# car_bluetooth_v1_1.net
KiCad netlist of a schematic drawn in EAGLE
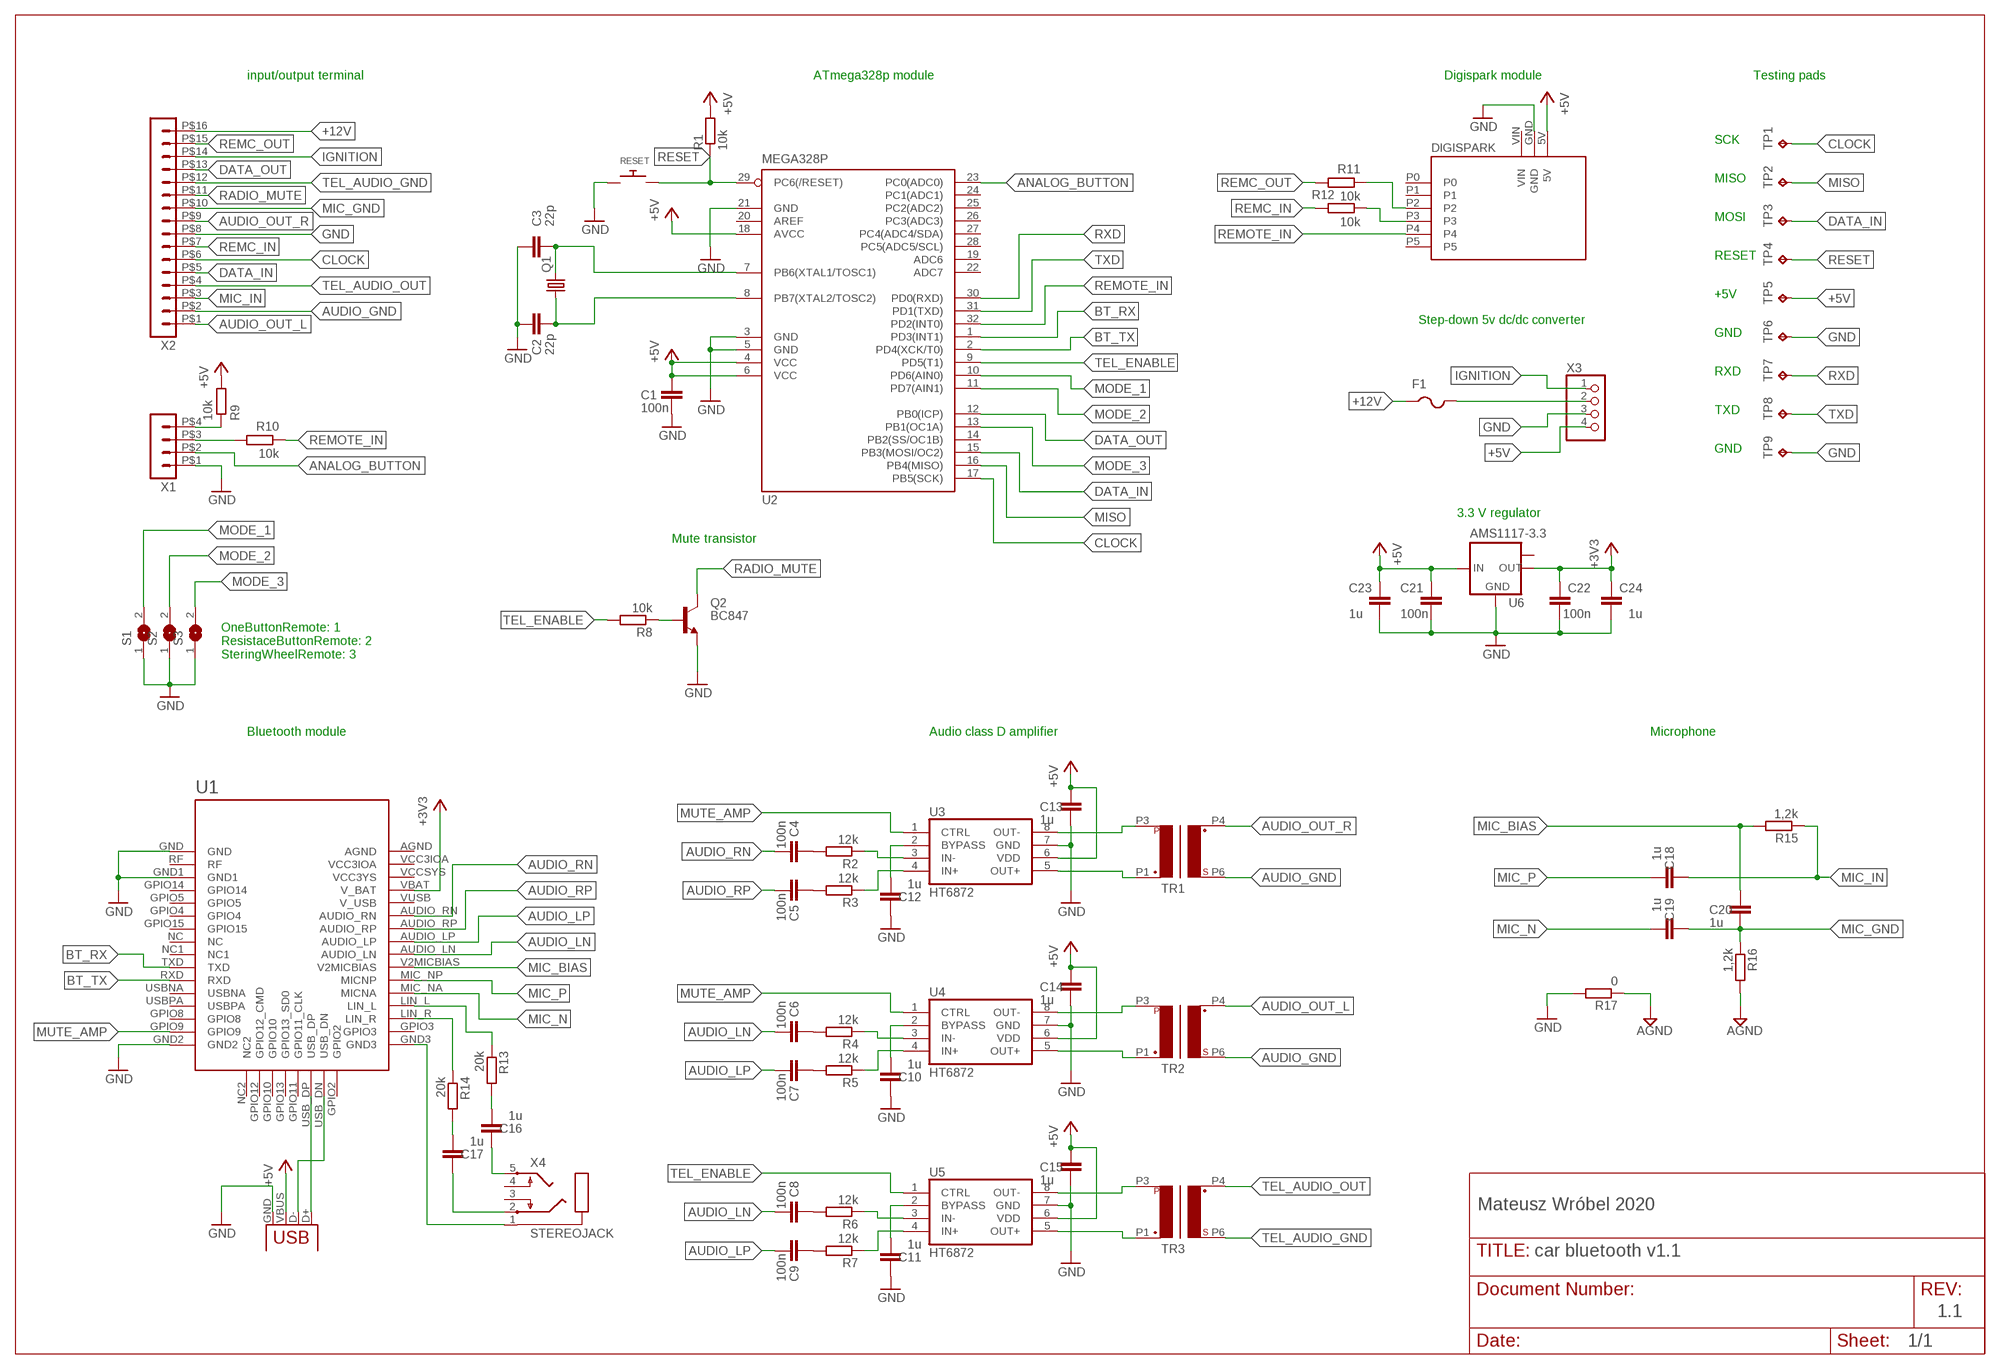
[diagram p0: schematic, sheet 1]

(export (version "E")
  (design (tool "Eeschema 10.0.6"))
  (components
    (comp (ref "C1")
      (value "100n")
      (footprint "eagle-import:C0805")
      (libsource (lib "eagle-import") (part "C-EUC0805"))
    )
    (comp (ref "C2")
      (value "22p")
      (footprint "eagle-import:C0805")
      (libsource (lib "eagle-import") (part "C-EUC0805"))
    )
    (comp (ref "C3")
      (value "22p")
      (footprint "eagle-import:C0805")
      (libsource (lib "eagle-import") (part "C-EUC0805"))
    )
    (comp (ref "C4")
      (value "100n")
      (footprint "eagle-import:C0805")
      (libsource (lib "eagle-import") (part "C-EUC0805"))
    )
    (comp (ref "C5")
      (value "100n")
      (footprint "eagle-import:C0805")
      (libsource (lib "eagle-import") (part "C-EUC0805"))
    )
    (comp (ref "C6")
      (value "100n")
      (footprint "eagle-import:C0805")
      (libsource (lib "eagle-import") (part "C-EUC0805"))
    )
    (comp (ref "C7")
      (value "100n")
      (footprint "eagle-import:C0805")
      (libsource (lib "eagle-import") (part "C-EUC0805"))
    )
    (comp (ref "C8")
      (value "100n")
      (footprint "eagle-import:C0805")
      (libsource (lib "eagle-import") (part "C-EUC0805"))
    )
    (comp (ref "C9")
      (value "100n")
      (footprint "eagle-import:C0805")
      (libsource (lib "eagle-import") (part "C-EUC0805"))
    )
    (comp (ref "C10")
      (value "1u")
      (footprint "eagle-import:C0805")
      (libsource (lib "eagle-import") (part "C-EUC0805"))
    )
    (comp (ref "C11")
      (value "1u")
      (footprint "eagle-import:C0805")
      (libsource (lib "eagle-import") (part "C-EUC0805"))
    )
    (comp (ref "C12")
      (value "1u")
      (footprint "eagle-import:C0805")
      (libsource (lib "eagle-import") (part "C-EUC0805"))
    )
    (comp (ref "C13")
      (value "1u")
      (footprint "eagle-import:C0805")
      (libsource (lib "eagle-import") (part "C-EUC0805"))
    )
    (comp (ref "C14")
      (value "1u")
      (footprint "eagle-import:C0805")
      (libsource (lib "eagle-import") (part "C-EUC0805"))
    )
    (comp (ref "C15")
      (value "1u")
      (footprint "eagle-import:C0805")
      (libsource (lib "eagle-import") (part "C-EUC0805"))
    )
    (comp (ref "C16")
      (value "1u")
      (footprint "eagle-import:C0805")
      (libsource (lib "eagle-import") (part "C-EUC0805"))
    )
    (comp (ref "C17")
      (value "1u")
      (footprint "eagle-import:C0805")
      (libsource (lib "eagle-import") (part "C-EUC0805"))
    )
    (comp (ref "C18")
      (value "1u")
      (footprint "eagle-import:C0805")
      (libsource (lib "eagle-import") (part "C-EUC0805"))
    )
    (comp (ref "C19")
      (value "1u")
      (footprint "eagle-import:C0805")
      (libsource (lib "eagle-import") (part "C-EUC0805"))
    )
    (comp (ref "C20")
      (value "1u")
      (footprint "eagle-import:C0805")
      (libsource (lib "eagle-import") (part "C-EUC0805"))
    )
    (comp (ref "C21")
      (value "100n")
      (footprint "eagle-import:C0805")
      (libsource (lib "eagle-import") (part "C-EUC0805"))
    )
    (comp (ref "C22")
      (value "100n")
      (footprint "eagle-import:C0805")
      (libsource (lib "eagle-import") (part "C-EUC0805"))
    )
    (comp (ref "C23")
      (value "1u")
      (footprint "eagle-import:C0805")
      (libsource (lib "eagle-import") (part "C-EUC0805"))
    )
    (comp (ref "C24")
      (value "1u")
      (footprint "eagle-import:C0805")
      (libsource (lib "eagle-import") (part "C-EUC0805"))
    )
    (comp (ref "F1")
      (value "PTCFUSE-1206")
      (footprint "eagle-import:R1206")
      (libsource (lib "eagle-import") (part "PTCFUSE-1206"))
    )
    (comp (ref "Q1")
      (value "CRYSTALHC49S")
      (footprint "eagle-import:HC49_S")
      (libsource (lib "eagle-import") (part "CRYSTALHC49S"))
    )
    (comp (ref "Q2")
      (value "BC847")
      (footprint "eagle-import:SOT23")
      (libsource (lib "eagle-import") (part "BC847SMDALT1"))
    )
    (comp (ref "R1")
      (value "10k")
      (footprint "eagle-import:R0805")
      (libsource (lib "eagle-import") (part "R-EU_R0805"))
    )
    (comp (ref "R2")
      (value "12k")
      (footprint "eagle-import:R0805")
      (libsource (lib "eagle-import") (part "R-EU_R0805"))
    )
    (comp (ref "R3")
      (value "12k")
      (footprint "eagle-import:R0805")
      (libsource (lib "eagle-import") (part "R-EU_R0805"))
    )
    (comp (ref "R4")
      (value "12k")
      (footprint "eagle-import:R0805")
      (libsource (lib "eagle-import") (part "R-EU_R0805"))
    )
    (comp (ref "R5")
      (value "12k")
      (footprint "eagle-import:R0805")
      (libsource (lib "eagle-import") (part "R-EU_R0805"))
    )
    (comp (ref "R6")
      (value "12k")
      (footprint "eagle-import:R0805")
      (libsource (lib "eagle-import") (part "R-EU_R0805"))
    )
    (comp (ref "R7")
      (value "12k")
      (footprint "eagle-import:R0805")
      (libsource (lib "eagle-import") (part "R-EU_R0805"))
    )
    (comp (ref "R8")
      (value "10k")
      (footprint "eagle-import:R0805")
      (libsource (lib "eagle-import") (part "R-EU_R0805"))
    )
    (comp (ref "R9")
      (value "10k")
      (footprint "eagle-import:R0805")
      (libsource (lib "eagle-import") (part "R-EU_R0805"))
    )
    (comp (ref "R10")
      (value "10k")
      (footprint "eagle-import:R0805")
      (libsource (lib "eagle-import") (part "R-EU_R0805"))
    )
    (comp (ref "R11")
      (value "10k")
      (footprint "eagle-import:R0805")
      (libsource (lib "eagle-import") (part "R-EU_R0805"))
    )
    (comp (ref "R12")
      (value "10k")
      (footprint "eagle-import:R0805")
      (libsource (lib "eagle-import") (part "R-EU_R0805"))
    )
    (comp (ref "R13")
      (value "20k")
      (footprint "eagle-import:R0805")
      (libsource (lib "eagle-import") (part "R-EU_R0805"))
    )
    (comp (ref "R14")
      (value "20k")
      (footprint "eagle-import:R0805")
      (libsource (lib "eagle-import") (part "R-EU_R0805"))
    )
    (comp (ref "R15")
      (value "1,2k")
      (footprint "eagle-import:R0805")
      (libsource (lib "eagle-import") (part "R-EU_R0805"))
    )
    (comp (ref "R16")
      (value "1,2k")
      (footprint "eagle-import:R0805")
      (libsource (lib "eagle-import") (part "R-EU_R0805"))
    )
    (comp (ref "R17")
      (value "0")
      (footprint "eagle-import:R0805")
      (libsource (lib "eagle-import") (part "R-EU_R0805"))
    )
    (comp (ref "RESET")
      (value "SWITCH_PUSHBUTTONSOFTTOUCHSMD_SJ")
      (footprint "eagle-import:PUSHBUTTON_SMD_SJ")
      (libsource (lib "eagle-import") (part "SWITCH_PUSHBUTTONSOFTTOUCHSMD_SJ"))
    )
    (comp (ref "S1") (value "SJ") (footprint "eagle-import:SJ") (libsource (lib "eagle-import") (part "SJ")))
    (comp (ref "S2") (value "SJ") (footprint "eagle-import:SJ") (libsource (lib "eagle-import") (part "SJ")))
    (comp (ref "S3") (value "SJ") (footprint "eagle-import:SJ") (libsource (lib "eagle-import") (part "SJ")))
    (comp (ref "TP1")
      (value "TPB1,27")
      (footprint "eagle-import:B1,27")
      (libsource (lib "eagle-import") (part "TPB1,27"))
    )
    (comp (ref "TP2")
      (value "TPB1,27")
      (footprint "eagle-import:B1,27")
      (libsource (lib "eagle-import") (part "TPB1,27"))
    )
    (comp (ref "TP3")
      (value "TPB1,27")
      (footprint "eagle-import:B1,27")
      (libsource (lib "eagle-import") (part "TPB1,27"))
    )
    (comp (ref "TP4")
      (value "TPB1,27")
      (footprint "eagle-import:B1,27")
      (libsource (lib "eagle-import") (part "TPB1,27"))
    )
    (comp (ref "TP5")
      (value "TPB1,27")
      (footprint "eagle-import:B1,27")
      (libsource (lib "eagle-import") (part "TPB1,27"))
    )
    (comp (ref "TP6")
      (value "TPB1,27")
      (footprint "eagle-import:B1,27")
      (libsource (lib "eagle-import") (part "TPB1,27"))
    )
    (comp (ref "TP7")
      (value "TPB1,27")
      (footprint "eagle-import:B1,27")
      (libsource (lib "eagle-import") (part "TPB1,27"))
    )
    (comp (ref "TP8")
      (value "TPB1,27")
      (footprint "eagle-import:B1,27")
      (libsource (lib "eagle-import") (part "TPB1,27"))
    )
    (comp (ref "TP9")
      (value "TPB1,27")
      (footprint "eagle-import:B1,27")
      (libsource (lib "eagle-import") (part "TPB1,27"))
    )
    (comp (ref "TR1")
      (value "AUDIO_R")
      (footprint "eagle-import:EI14")
      (libsource (lib "eagle-import") (part "AUDIO_ISOLATION_TRANSFORMER_EI14"))
    )
    (comp (ref "TR2")
      (value "AUDIO_L")
      (footprint "eagle-import:EI14")
      (libsource (lib "eagle-import") (part "AUDIO_ISOLATION_TRANSFORMER_EI14"))
    )
    (comp (ref "TR3")
      (value "AUDIO_MIC")
      (footprint "eagle-import:EI14")
      (libsource (lib "eagle-import") (part "AUDIO_ISOLATION_TRANSFORMER_EI14"))
    )
    (comp (ref "U$7")
      (value "DIGISPARK")
      (footprint "eagle-import:DIGISPARK")
      (libsource (lib "eagle-import") (part "DIGISPARK"))
    )
    (comp (ref "U1")
      (value "BK3266_BOARD")
      (footprint "eagle-import:40PIN_BOARD")
      (libsource (lib "eagle-import") (part "BK3266_BOARD"))
    )
    (comp (ref "U2")
      (value "MEGA328P")
      (footprint "eagle-import:TQFP32-08")
      (fields (field (name "MPN") "ATMEGA8-16AU"))
      (libsource (lib "eagle-import") (part "MEGA8-AI"))
    )
    (comp (ref "U3")
      (value "HT6872")
      (footprint "eagle-import:SO8")
      (libsource (lib "eagle-import") (part "HT6872"))
    )
    (comp (ref "U4")
      (value "HT6872")
      (footprint "eagle-import:SO8")
      (libsource (lib "eagle-import") (part "HT6872"))
    )
    (comp (ref "U5")
      (value "HT6872")
      (footprint "eagle-import:SO8")
      (libsource (lib "eagle-import") (part "HT6872"))
    )
    (comp (ref "U6")
      (value "AMS1117-3.3")
      (footprint "eagle-import:SOT223")
      (libsource (lib "eagle-import") (part "LM1117MPX-3.3"))
    )
    (comp (ref "X1")
      (value "HEADER_POS4_43045-0401")
      (footprint "eagle-import:43045-0400")
      (libsource (lib "eagle-import") (part "HEADER_POS4_?43045-0401"))
    )
    (comp (ref "X2")
      (value "HEADER_POS16_43045-1600")
      (footprint "eagle-import:43045-1600")
      (libsource (lib "eagle-import") (part "HEADER_POS16_?43045-1600"))
    )
    (comp (ref "X3")
      (value "PINHD-1X4")
      (footprint "eagle-import:1X04")
      (libsource (lib "eagle-import") (part "PINHD-1X4"))
    )
    (comp (ref "X4")
      (value "STEREOJACK")
      (footprint "eagle-import:STX3100")
      (libsource (lib "eagle-import") (part "STEREOJACK"))
    )
    (comp (ref "X5")
      (value "USB-A-H")
      (footprint "eagle-import:USB-A-H")
      (libsource (lib "eagle-import") (part "USB-A-H"))
    )
  )
  (nets
    (net (code "1") (name "+3V3") (class "Default")
      (node (ref "C22") (pin "2") (pinfunction "2_2") (pintype "passive"))
      (node (ref "C24") (pin "2") (pinfunction "2_2") (pintype "passive"))
      (node (ref "U1") (pin "VBAT") (pinfunction "V_BAT_VBAT") (pintype "bidirectional"))
      (node (ref "U6") (pin "2") (pinfunction "OUT_2") (pintype "passive"))
    )
    (net (code "2") (name "+5V") (class "Default")
      (node (ref "C1") (pin "1") (pinfunction "1_1") (pintype "passive"))
      (node (ref "C13") (pin "1") (pinfunction "1_1") (pintype "passive"))
      (node (ref "C14") (pin "1") (pinfunction "1_1") (pintype "passive"))
      (node (ref "C15") (pin "1") (pinfunction "1_1") (pintype "passive"))
      (node (ref "C21") (pin "1") (pinfunction "1_1") (pintype "passive"))
      (node (ref "C23") (pin "1") (pinfunction "1_1") (pintype "passive"))
      (node (ref "R1") (pin "2") (pinfunction "2_2") (pintype "passive"))
      (node (ref "R9") (pin "1") (pinfunction "1_1") (pintype "passive"))
      (node (ref "TP5") (pin "TP") (pinfunction "TP_TP") (pintype "input"))
      (node (ref "U$7") (pin "5V") (pinfunction "5V_5V") (pintype "bidirectional"))
      (node (ref "U2") (pin "18") (pinfunction "AVCC_18") (pintype "power_in"))
      (node (ref "U2") (pin "4") (pinfunction "VCC_4") (pintype "power_in"))
      (node (ref "U2") (pin "6") (pinfunction "VCC_6") (pintype "power_in"))
      (node (ref "U3") (pin "6") (pinfunction "VDD_6") (pintype "power_in"))
      (node (ref "U4") (pin "6") (pinfunction "VDD_6") (pintype "power_in"))
      (node (ref "U5") (pin "6") (pinfunction "VDD_6") (pintype "power_in"))
      (node (ref "U6") (pin "3") (pinfunction "IN_3") (pintype "input"))
      (node (ref "X3") (pin "4") (pinfunction "4_4") (pintype "passive"))
      (node (ref "X5") (pin "VBUS") (pinfunction "VBUS_VBUS") (pintype "bidirectional"))
    )
    (net (code "3") (name "+12V") (class "Default")
      (node (ref "F1") (pin "1") (pinfunction "1_1") (pintype "passive"))
      (node (ref "X2") (pin "P$16") (pinfunction "16_P$16") (pintype "passive"))
    )
    (net (code "4") (name "AGND") (class "Default")
      (node (ref "R16") (pin "2") (pinfunction "2_2") (pintype "passive"))
      (node (ref "R17") (pin "1") (pinfunction "1_1") (pintype "passive"))
    )
    (net (code "5") (name "ANALOG_BUTTON") (class "Default")
      (node (ref "U2") (pin "23") (pinfunction "PC0(ADC0)_23") (pintype "bidirectional"))
      (node (ref "X1") (pin "P$2") (pinfunction "2_P$2") (pintype "passive"))
    )
    (net (code "6") (name "AUDIO_GND") (class "Default")
      (node (ref "TR1") (pin "P6") (pinfunction "P4_P6") (pintype "bidirectional"))
      (node (ref "TR2") (pin "P6") (pinfunction "P4_P6") (pintype "bidirectional"))
      (node (ref "X2") (pin "P$2") (pinfunction "2_P$2") (pintype "passive"))
    )
    (net (code "7") (name "AUDIO_LN") (class "Default")
      (node (ref "C6") (pin "2") (pinfunction "2_2") (pintype "passive"))
      (node (ref "C8") (pin "2") (pinfunction "2_2") (pintype "passive"))
      (node (ref "U1") (pin "AUDIO_LN") (pinfunction "AUDIO_LN_AUDIO_LN") (pintype "bidirectional"))
    )
    (net (code "8") (name "AUDIO_LP") (class "Default")
      (node (ref "C7") (pin "2") (pinfunction "2_2") (pintype "passive"))
      (node (ref "C9") (pin "2") (pinfunction "2_2") (pintype "passive"))
      (node (ref "U1") (pin "AUDIO_LP") (pinfunction "AUDIO_LP_AUDIO_LP") (pintype "bidirectional"))
    )
    (net (code "9") (name "AUDIO_OUT_L") (class "Default")
      (node (ref "TR2") (pin "P4") (pinfunction "P3_P4") (pintype "bidirectional"))
      (node (ref "X2") (pin "P$1") (pinfunction "1_P$1") (pintype "passive"))
    )
    (net (code "10") (name "AUDIO_OUT_R") (class "Default")
      (node (ref "TR1") (pin "P4") (pinfunction "P3_P4") (pintype "bidirectional"))
      (node (ref "X2") (pin "P$9") (pinfunction "9_P$9") (pintype "passive"))
    )
    (net (code "11") (name "AUDIO_RN") (class "Default")
      (node (ref "C4") (pin "2") (pinfunction "2_2") (pintype "passive"))
      (node (ref "U1") (pin "AUDIO_RN") (pinfunction "AUDIO_RN_AUDIO_RN") (pintype "bidirectional"))
    )
    (net (code "12") (name "AUDIO_RP") (class "Default")
      (node (ref "C5") (pin "2") (pinfunction "2_2") (pintype "passive"))
      (node (ref "U1") (pin "AUDIO_RP") (pinfunction "AUDIO_RP_AUDIO_RP") (pintype "bidirectional"))
    )
    (net (code "13") (name "BT_RX") (class "Default")
      (node (ref "U1") (pin "TXD") (pinfunction "TXD_TXD") (pintype "bidirectional"))
      (node (ref "U2") (pin "1") (pinfunction "PD3(INT1)_1") (pintype "bidirectional"))
    )
    (net (code "14") (name "BT_TX") (class "Default")
      (node (ref "U1") (pin "RXD") (pinfunction "RXD_RXD") (pintype "bidirectional"))
      (node (ref "U2") (pin "2") (pinfunction "PD4(XCK/T0)_2") (pintype "bidirectional"))
    )
    (net (code "15") (name "CLOCK") (class "Default")
      (node (ref "TP1") (pin "TP") (pinfunction "TP_TP") (pintype "input"))
      (node (ref "U2") (pin "17") (pinfunction "PB5(SCK)_17") (pintype "bidirectional"))
      (node (ref "X2") (pin "P$6") (pinfunction "6_P$6") (pintype "passive"))
    )
    (net (code "16") (name "DATA_IN") (class "Default")
      (node (ref "TP3") (pin "TP") (pinfunction "TP_TP") (pintype "input"))
      (node (ref "U2") (pin "15") (pinfunction "PB3(MOSI/OC2)_15") (pintype "bidirectional"))
      (node (ref "X2") (pin "P$5") (pinfunction "5_P$5") (pintype "passive"))
    )
    (net (code "17") (name "DATA_OUT") (class "Default")
      (node (ref "U2") (pin "12") (pinfunction "PB0(ICP)_12") (pintype "bidirectional"))
      (node (ref "X2") (pin "P$13") (pinfunction "13_P$13") (pintype "passive"))
    )
    (net (code "18") (name "GND") (class "Default")
      (node (ref "C1") (pin "2") (pinfunction "2_2") (pintype "passive"))
      (node (ref "C10") (pin "1") (pinfunction "1_1") (pintype "passive"))
      (node (ref "C11") (pin "1") (pinfunction "1_1") (pintype "passive"))
      (node (ref "C12") (pin "1") (pinfunction "1_1") (pintype "passive"))
      (node (ref "C13") (pin "2") (pinfunction "2_2") (pintype "passive"))
      (node (ref "C14") (pin "2") (pinfunction "2_2") (pintype "passive"))
      (node (ref "C15") (pin "2") (pinfunction "2_2") (pintype "passive"))
      (node (ref "C2") (pin "1") (pinfunction "1_1") (pintype "passive"))
      (node (ref "C21") (pin "2") (pinfunction "2_2") (pintype "passive"))
      (node (ref "C22") (pin "1") (pinfunction "1_1") (pintype "passive"))
      (node (ref "C23") (pin "2") (pinfunction "2_2") (pintype "passive"))
      (node (ref "C24") (pin "1") (pinfunction "1_1") (pintype "passive"))
      (node (ref "C3") (pin "1") (pinfunction "1_1") (pintype "passive"))
      (node (ref "Q2") (pin "2") (pinfunction "E_2") (pintype "passive"))
      (node (ref "R17") (pin "2") (pinfunction "2_2") (pintype "passive"))
      (node (ref "RESET") (pin "P$1") (pinfunction "P$1_P$1") (pintype "passive"))
      (node (ref "S1") (pin "1") (pinfunction "1_1") (pintype "passive"))
      (node (ref "S2") (pin "1") (pinfunction "1_1") (pintype "passive"))
      (node (ref "S3") (pin "1") (pinfunction "1_1") (pintype "passive"))
      (node (ref "TP6") (pin "TP") (pinfunction "TP_TP") (pintype "input"))
      (node (ref "TP9") (pin "TP") (pinfunction "TP_TP") (pintype "input"))
      (node (ref "U$7") (pin "GND") (pinfunction "GND_GND") (pintype "bidirectional"))
      (node (ref "U1") (pin "GND") (pinfunction "GND_GND") (pintype "bidirectional"))
      (node (ref "U1") (pin "GND1") (pinfunction "GND1_GND1") (pintype "bidirectional"))
      (node (ref "U1") (pin "GND2") (pinfunction "GND2_GND2") (pintype "bidirectional"))
      (node (ref "U2") (pin "21") (pinfunction "GND_21") (pintype "power_in"))
      (node (ref "U2") (pin "3") (pinfunction "GND_3") (pintype "power_in"))
      (node (ref "U2") (pin "5") (pinfunction "GND_5") (pintype "power_in"))
      (node (ref "U3") (pin "7") (pinfunction "GND_7") (pintype "power_in"))
      (node (ref "U4") (pin "7") (pinfunction "GND_7") (pintype "power_in"))
      (node (ref "U5") (pin "7") (pinfunction "GND_7") (pintype "power_in"))
      (node (ref "U6") (pin "1") (pinfunction "GND_1") (pintype "input"))
      (node (ref "X1") (pin "P$1") (pinfunction "1_P$1") (pintype "passive"))
      (node (ref "X2") (pin "P$8") (pinfunction "8_P$8") (pintype "passive"))
      (node (ref "X3") (pin "3") (pinfunction "3_3") (pintype "passive"))
      (node (ref "X5") (pin "GND") (pinfunction "GND_GND") (pintype "bidirectional"))
    )
    (net (code "19") (name "IGNITION") (class "Default")
      (node (ref "X2") (pin "P$14") (pinfunction "14_P$14") (pintype "passive"))
      (node (ref "X3") (pin "1") (pinfunction "1_1") (pintype "passive"))
    )
    (net (code "20") (name "MIC_BIAS") (class "Default")
      (node (ref "C20") (pin "1") (pinfunction "1_1") (pintype "passive"))
      (node (ref "R15") (pin "2") (pinfunction "2_2") (pintype "passive"))
      (node (ref "U1") (pin "V2MICBIAS") (pinfunction "V2MICBIAS_V2MICBIAS") (pintype "bidirectional"))
    )
    (net (code "21") (name "MIC_GND") (class "Default")
      (node (ref "C19") (pin "1") (pinfunction "1_1") (pintype "passive"))
      (node (ref "C20") (pin "2") (pinfunction "2_2") (pintype "passive"))
      (node (ref "R16") (pin "1") (pinfunction "1_1") (pintype "passive"))
      (node (ref "X2") (pin "P$10") (pinfunction "10_P$10") (pintype "passive"))
    )
    (net (code "22") (name "MIC_IN") (class "Default")
      (node (ref "C18") (pin "1") (pinfunction "1_1") (pintype "passive"))
      (node (ref "R15") (pin "1") (pinfunction "1_1") (pintype "passive"))
      (node (ref "X2") (pin "P$3") (pinfunction "3_P$3") (pintype "passive"))
    )
    (net (code "23") (name "MIC_N") (class "Default")
      (node (ref "C19") (pin "2") (pinfunction "2_2") (pintype "passive"))
      (node (ref "U1") (pin "MIC_NA") (pinfunction "MICNA_MIC_NA") (pintype "bidirectional"))
    )
    (net (code "24") (name "MIC_P") (class "Default")
      (node (ref "C18") (pin "2") (pinfunction "2_2") (pintype "passive"))
      (node (ref "U1") (pin "MIC_NP") (pinfunction "MICNP_MIC_NP") (pintype "bidirectional"))
    )
    (net (code "25") (name "MISO") (class "Default")
      (node (ref "TP2") (pin "TP") (pinfunction "TP_TP") (pintype "input"))
      (node (ref "U2") (pin "16") (pinfunction "PB4(MISO)_16") (pintype "bidirectional"))
    )
    (net (code "26") (name "MODE_1") (class "Default")
      (node (ref "S1") (pin "2") (pinfunction "2_2") (pintype "passive"))
      (node (ref "U2") (pin "10") (pinfunction "PD6(AIN0)_10") (pintype "bidirectional"))
    )
    (net (code "27") (name "MODE_2") (class "Default")
      (node (ref "S2") (pin "2") (pinfunction "2_2") (pintype "passive"))
      (node (ref "U2") (pin "11") (pinfunction "PD7(AIN1)_11") (pintype "bidirectional"))
    )
    (net (code "28") (name "MODE_3") (class "Default")
      (node (ref "S3") (pin "2") (pinfunction "2_2") (pintype "passive"))
      (node (ref "U2") (pin "13") (pinfunction "PB1(OC1A)_13") (pintype "bidirectional"))
    )
    (net (code "29") (name "MUTE_AMP") (class "Default")
      (node (ref "U1") (pin "GPIO9") (pinfunction "GPIO9_GPIO9") (pintype "bidirectional"))
      (node (ref "U3") (pin "1") (pinfunction "CTRL_1") (pintype "bidirectional"))
      (node (ref "U4") (pin "1") (pinfunction "CTRL_1") (pintype "bidirectional"))
    )
    (net (code "30") (name "Net-(C4-Pad1)") (class "Default")
      (node (ref "C4") (pin "1") (pinfunction "1_1") (pintype "passive"))
      (node (ref "R2") (pin "2") (pinfunction "2_2") (pintype "passive"))
    )
    (net (code "31") (name "Net-(C5-Pad1)") (class "Default")
      (node (ref "C5") (pin "1") (pinfunction "1_1") (pintype "passive"))
      (node (ref "R3") (pin "2") (pinfunction "2_2") (pintype "passive"))
    )
    (net (code "32") (name "Net-(C6-Pad1)") (class "Default")
      (node (ref "C6") (pin "1") (pinfunction "1_1") (pintype "passive"))
      (node (ref "R4") (pin "2") (pinfunction "2_2") (pintype "passive"))
    )
    (net (code "33") (name "Net-(C7-Pad1)") (class "Default")
      (node (ref "C7") (pin "1") (pinfunction "1_1") (pintype "passive"))
      (node (ref "R5") (pin "2") (pinfunction "2_2") (pintype "passive"))
    )
    (net (code "34") (name "Net-(C8-Pad1)") (class "Default")
      (node (ref "C8") (pin "1") (pinfunction "1_1") (pintype "passive"))
      (node (ref "R6") (pin "2") (pinfunction "2_2") (pintype "passive"))
    )
    (net (code "35") (name "Net-(C9-Pad1)") (class "Default")
      (node (ref "C9") (pin "1") (pinfunction "1_1") (pintype "passive"))
      (node (ref "R7") (pin "2") (pinfunction "2_2") (pintype "passive"))
    )
    (net (code "36") (name "Net-(C16-Pad1)") (class "Default")
      (node (ref "C16") (pin "1") (pinfunction "1_1") (pintype "passive"))
      (node (ref "X4") (pin "5") (pinfunction "5_5") (pintype "passive"))
    )
    (net (code "37") (name "Net-(C16-Pad2)") (class "Default")
      (node (ref "C16") (pin "2") (pinfunction "2_2") (pintype "passive"))
      (node (ref "R13") (pin "2") (pinfunction "2_2") (pintype "passive"))
    )
    (net (code "38") (name "Net-(C17-Pad1)") (class "Default")
      (node (ref "C17") (pin "1") (pinfunction "1_1") (pintype "passive"))
      (node (ref "X4") (pin "2") (pinfunction "2_2") (pintype "passive"))
    )
    (net (code "39") (name "Net-(C17-Pad2)") (class "Default")
      (node (ref "C17") (pin "2") (pinfunction "2_2") (pintype "passive"))
      (node (ref "R14") (pin "2") (pinfunction "2_2") (pintype "passive"))
    )
    (net (code "40") (name "Net-(F1-Pad2)") (class "Default")
      (node (ref "F1") (pin "2") (pinfunction "2_2") (pintype "passive"))
      (node (ref "X3") (pin "2") (pinfunction "2_2") (pintype "passive"))
    )
    (net (code "41") (name "Net-(Q2-B)") (class "Default")
      (node (ref "Q2") (pin "1") (pinfunction "B_1") (pintype "passive"))
      (node (ref "R8") (pin "1") (pinfunction "1_1") (pintype "passive"))
    )
    (net (code "42") (name "Net-(R11-Pad2)") (class "Default")
      (node (ref "R11") (pin "2") (pinfunction "2_2") (pintype "passive"))
      (node (ref "U$7") (pin "P2") (pinfunction "P2_P2") (pintype "bidirectional"))
    )
    (net (code "43") (name "Net-(R12-Pad2)") (class "Default")
      (node (ref "R12") (pin "2") (pinfunction "2_2") (pintype "passive"))
      (node (ref "U$7") (pin "P3") (pinfunction "P3_P3") (pintype "bidirectional"))
    )
    (net (code "44") (name "Net-(R13-Pad1)") (class "Default")
      (node (ref "R13") (pin "1") (pinfunction "1_1") (pintype "passive"))
      (node (ref "U1") (pin "LIN_L") (pinfunction "LIN_L_LIN_L") (pintype "bidirectional"))
    )
    (net (code "45") (name "Net-(R14-Pad1)") (class "Default")
      (node (ref "R14") (pin "1") (pinfunction "1_1") (pintype "passive"))
      (node (ref "U1") (pin "LIN_R") (pinfunction "LIN_R_LIN_R") (pintype "bidirectional"))
    )
    (net (code "46") (name "Net-(TR1-P2)") (class "Default")
      (node (ref "TR1") (pin "P3") (pinfunction "P2_P3") (pintype "bidirectional"))
      (node (ref "U3") (pin "8") (pinfunction "OUT-_8") (pintype "output"))
    )
    (net (code "47") (name "Net-(TR2-P2)") (class "Default")
      (node (ref "TR2") (pin "P3") (pinfunction "P2_P3") (pintype "bidirectional"))
      (node (ref "U4") (pin "8") (pinfunction "OUT-_8") (pintype "output"))
    )
    (net (code "48") (name "Net-(TR3-P2)") (class "Default")
      (node (ref "TR3") (pin "P3") (pinfunction "P2_P3") (pintype "bidirectional"))
      (node (ref "U5") (pin "8") (pinfunction "OUT-_8") (pintype "output"))
    )
    (net (code "49") (name "Net-(U1-PadGND3)") (class "Default")
      (node (ref "U1") (pin "GND3") (pinfunction "GND3_GND3") (pintype "bidirectional"))
      (node (ref "X4") (pin "1") (pinfunction "1_1") (pintype "passive"))
    )
    (net (code "50") (name "Net-(U1-PadUSB_DN)") (class "Default")
      (node (ref "U1") (pin "USB_DN") (pinfunction "USB_DN_USB_DN") (pintype "bidirectional"))
      (node (ref "X5") (pin "D-") (pinfunction "D-_D-") (pintype "bidirectional"))
    )
    (net (code "51") (name "Net-(U1-PadUSB_DP)") (class "Default")
      (node (ref "U1") (pin "USB_DP") (pinfunction "USB_DP_USB_DP") (pintype "bidirectional"))
      (node (ref "X5") (pin "D+") (pinfunction "D+_D+") (pintype "bidirectional"))
    )
    (net (code "52") (name "Net-(U2-PB6(XTAL1{slash}TOSC1))") (class "Default")
      (node (ref "C3") (pin "2") (pinfunction "2_2") (pintype "passive"))
      (node (ref "Q1") (pin "2") (pinfunction "2_2") (pintype "passive"))
      (node (ref "U2") (pin "7") (pinfunction "PB6(XTAL1/TOSC1)_7") (pintype "bidirectional"))
    )
    (net (code "53") (name "Net-(U2-PB7(XTAL2{slash}TOSC2))") (class "Default")
      (node (ref "C2") (pin "2") (pinfunction "2_2") (pintype "passive"))
      (node (ref "Q1") (pin "1") (pinfunction "1_1") (pintype "passive"))
      (node (ref "U2") (pin "8") (pinfunction "PB7(XTAL2/TOSC2)_8") (pintype "bidirectional"))
    )
    (net (code "54") (name "Net-(U3-BYPASS)") (class "Default")
      (node (ref "C12") (pin "2") (pinfunction "2_2") (pintype "passive"))
      (node (ref "U3") (pin "2") (pinfunction "BYPASS_2") (pintype "input"))
    )
    (net (code "55") (name "Net-(U3-IN+)") (class "Default")
      (node (ref "R3") (pin "1") (pinfunction "1_1") (pintype "passive"))
      (node (ref "U3") (pin "4") (pinfunction "IN+_4") (pintype "input"))
    )
    (net (code "56") (name "Net-(U3-IN-)") (class "Default")
      (node (ref "R2") (pin "1") (pinfunction "1_1") (pintype "passive"))
      (node (ref "U3") (pin "3") (pinfunction "IN-_3") (pintype "input"))
    )
    (net (code "57") (name "Net-(U3-OUT+)") (class "Default")
      (node (ref "TR1") (pin "P1") (pinfunction "P1_P1") (pintype "bidirectional"))
      (node (ref "U3") (pin "5") (pinfunction "OUT+_5") (pintype "output"))
    )
    (net (code "58") (name "Net-(U4-BYPASS)") (class "Default")
      (node (ref "C10") (pin "2") (pinfunction "2_2") (pintype "passive"))
      (node (ref "U4") (pin "2") (pinfunction "BYPASS_2") (pintype "input"))
    )
    (net (code "59") (name "Net-(U4-IN+)") (class "Default")
      (node (ref "R5") (pin "1") (pinfunction "1_1") (pintype "passive"))
      (node (ref "U4") (pin "4") (pinfunction "IN+_4") (pintype "input"))
    )
    (net (code "60") (name "Net-(U4-IN-)") (class "Default")
      (node (ref "R4") (pin "1") (pinfunction "1_1") (pintype "passive"))
      (node (ref "U4") (pin "3") (pinfunction "IN-_3") (pintype "input"))
    )
    (net (code "61") (name "Net-(U4-OUT+)") (class "Default")
      (node (ref "TR2") (pin "P1") (pinfunction "P1_P1") (pintype "bidirectional"))
      (node (ref "U4") (pin "5") (pinfunction "OUT+_5") (pintype "output"))
    )
    (net (code "62") (name "Net-(U5-BYPASS)") (class "Default")
      (node (ref "C11") (pin "2") (pinfunction "2_2") (pintype "passive"))
      (node (ref "U5") (pin "2") (pinfunction "BYPASS_2") (pintype "input"))
    )
    (net (code "63") (name "Net-(U5-IN+)") (class "Default")
      (node (ref "R7") (pin "1") (pinfunction "1_1") (pintype "passive"))
      (node (ref "U5") (pin "4") (pinfunction "IN+_4") (pintype "input"))
    )
    (net (code "64") (name "Net-(U5-IN-)") (class "Default")
      (node (ref "R6") (pin "1") (pinfunction "1_1") (pintype "passive"))
      (node (ref "U5") (pin "3") (pinfunction "IN-_3") (pintype "input"))
    )
    (net (code "65") (name "Net-(U5-OUT+)") (class "Default")
      (node (ref "TR3") (pin "P1") (pinfunction "P1_P1") (pintype "bidirectional"))
      (node (ref "U5") (pin "5") (pinfunction "OUT+_5") (pintype "output"))
    )
    (net (code "66") (name "Net-(X1-3)") (class "Default")
      (node (ref "R10") (pin "1") (pinfunction "1_1") (pintype "passive"))
      (node (ref "X1") (pin "P$3") (pinfunction "3_P$3") (pintype "passive"))
    )
    (net (code "67") (name "Net-(X1-4)") (class "Default")
      (node (ref "R9") (pin "2") (pinfunction "2_2") (pintype "passive"))
      (node (ref "X1") (pin "P$4") (pinfunction "4_P$4") (pintype "passive"))
    )
    (net (code "68") (name "RADIO_MUTE") (class "Default")
      (node (ref "Q2") (pin "3") (pinfunction "C_3") (pintype "passive"))
      (node (ref "X2") (pin "P$11") (pinfunction "11_P$11") (pintype "passive"))
    )
    (net (code "69") (name "REMC_IN") (class "Default")
      (node (ref "R12") (pin "1") (pinfunction "1_1") (pintype "passive"))
      (node (ref "X2") (pin "P$7") (pinfunction "7_P$7") (pintype "passive"))
    )
    (net (code "70") (name "REMC_OUT") (class "Default")
      (node (ref "R11") (pin "1") (pinfunction "1_1") (pintype "passive"))
      (node (ref "X2") (pin "P$15") (pinfunction "15_P$15") (pintype "passive"))
    )
    (net (code "71") (name "REMOTE_IN") (class "Default")
      (node (ref "R10") (pin "2") (pinfunction "2_2") (pintype "passive"))
      (node (ref "U$7") (pin "P4") (pinfunction "P4_P4") (pintype "bidirectional"))
      (node (ref "U2") (pin "32") (pinfunction "PD2(INT0)_32") (pintype "bidirectional"))
    )
    (net (code "72") (name "RESET") (class "Default")
      (node (ref "R1") (pin "1") (pinfunction "1_1") (pintype "passive"))
      (node (ref "RESET") (pin "P$2") (pinfunction "P$2_P$2") (pintype "passive"))
      (node (ref "TP4") (pin "TP") (pinfunction "TP_TP") (pintype "input"))
      (node (ref "U2") (pin "29") (pinfunction "PC6(/RESET)_29") (pintype "bidirectional"))
    )
    (net (code "73") (name "RXD") (class "Default")
      (node (ref "TP7") (pin "TP") (pinfunction "TP_TP") (pintype "input"))
      (node (ref "U2") (pin "30") (pinfunction "PD0(RXD)_30") (pintype "bidirectional"))
    )
    (net (code "74") (name "TEL_AUDIO_GND") (class "Default")
      (node (ref "TR3") (pin "P6") (pinfunction "P4_P6") (pintype "bidirectional"))
      (node (ref "X2") (pin "P$12") (pinfunction "12_P$12") (pintype "passive"))
    )
    (net (code "75") (name "TEL_AUDIO_OUT") (class "Default")
      (node (ref "TR3") (pin "P4") (pinfunction "P3_P4") (pintype "bidirectional"))
      (node (ref "X2") (pin "P$4") (pinfunction "4_P$4") (pintype "passive"))
    )
    (net (code "76") (name "TEL_ENABLE") (class "Default")
      (node (ref "R8") (pin "2") (pinfunction "2_2") (pintype "passive"))
      (node (ref "U2") (pin "9") (pinfunction "PD5(T1)_9") (pintype "bidirectional"))
      (node (ref "U5") (pin "1") (pinfunction "CTRL_1") (pintype "bidirectional"))
    )
    (net (code "77") (name "TXD") (class "Default")
      (node (ref "TP8") (pin "TP") (pinfunction "TP_TP") (pintype "input"))
      (node (ref "U2") (pin "31") (pinfunction "PD1(TXD)_31") (pintype "bidirectional"))
    )
    (net (code "78") (name "unconnected-(U$7-PadP0)") (class "Default")
      (node (ref "U$7") (pin "P0") (pinfunction "P0_P0") (pintype "bidirectional"))
    )
    (net (code "79") (name "unconnected-(U$7-PadP1)") (class "Default")
      (node (ref "U$7") (pin "P1") (pinfunction "P1_P1") (pintype "bidirectional"))
    )
    (net (code "80") (name "unconnected-(U$7-PadP5)") (class "Default")
      (node (ref "U$7") (pin "P5") (pinfunction "P5_P5") (pintype "bidirectional"))
    )
    (net (code "81") (name "unconnected-(U$7-PadVIN)") (class "Default")
      (node (ref "U$7") (pin "VIN") (pinfunction "VIN_VIN") (pintype "bidirectional"))
    )
    (net (code "82") (name "unconnected-(U1-GPIO11_CLK-PadGPIO11)") (class "Default")
      (node (ref "U1") (pin "GPIO11") (pinfunction "GPIO11_CLK_GPIO11") (pintype "bidirectional"))
    )
    (net (code "83") (name "unconnected-(U1-GPIO12_CMD-PadGPIO12)") (class "Default")
      (node (ref "U1") (pin "GPIO12") (pinfunction "GPIO12_CMD_GPIO12") (pintype "bidirectional"))
    )
    (net (code "84") (name "unconnected-(U1-GPIO13_SD0-PadGPIO13)") (class "Default")
      (node (ref "U1") (pin "GPIO13") (pinfunction "GPIO13_SD0_GPIO13") (pintype "bidirectional"))
    )
    (net (code "85") (name "unconnected-(U1-PadAGND)") (class "Default")
      (node (ref "U1") (pin "AGND") (pinfunction "AGND_AGND") (pintype "bidirectional"))
    )
    (net (code "86") (name "unconnected-(U1-PadGPIO2)") (class "Default")
      (node (ref "U1") (pin "GPIO2") (pinfunction "GPIO2_GPIO2") (pintype "bidirectional"))
    )
    (net (code "87") (name "unconnected-(U1-PadGPIO3)") (class "Default")
      (node (ref "U1") (pin "GPIO3") (pinfunction "GPIO3_GPIO3") (pintype "bidirectional"))
    )
    (net (code "88") (name "unconnected-(U1-PadGPIO4)") (class "Default")
      (node (ref "U1") (pin "GPIO4") (pinfunction "GPIO4_GPIO4") (pintype "bidirectional"))
    )
    (net (code "89") (name "unconnected-(U1-PadGPIO5)") (class "Default")
      (node (ref "U1") (pin "GPIO5") (pinfunction "GPIO5_GPIO5") (pintype "bidirectional"))
    )
    (net (code "90") (name "unconnected-(U1-PadGPIO8)") (class "Default")
      (node (ref "U1") (pin "GPIO8") (pinfunction "GPIO8_GPIO8") (pintype "bidirectional"))
    )
    (net (code "91") (name "unconnected-(U1-PadGPIO10)") (class "Default")
      (node (ref "U1") (pin "GPIO10") (pinfunction "GPIO10_GPIO10") (pintype "bidirectional"))
    )
    (net (code "92") (name "unconnected-(U1-PadGPIO14)") (class "Default")
      (node (ref "U1") (pin "GPIO14") (pinfunction "GPIO14_GPIO14") (pintype "bidirectional"))
    )
    (net (code "93") (name "unconnected-(U1-PadGPIO15)") (class "Default")
      (node (ref "U1") (pin "GPIO15") (pinfunction "GPIO15_GPIO15") (pintype "bidirectional"))
    )
    (net (code "94") (name "unconnected-(U1-PadNC)") (class "Default")
      (node (ref "U1") (pin "NC") (pinfunction "NC_NC") (pintype "bidirectional"))
    )
    (net (code "95") (name "unconnected-(U1-PadNC1)") (class "Default")
      (node (ref "U1") (pin "NC1") (pinfunction "NC1_NC1") (pintype "bidirectional"))
    )
    (net (code "96") (name "unconnected-(U1-PadNC2)") (class "Default")
      (node (ref "U1") (pin "NC2") (pinfunction "NC2_NC2") (pintype "bidirectional"))
    )
    (net (code "97") (name "unconnected-(U1-PadRF)") (class "Default")
      (node (ref "U1") (pin "RF") (pinfunction "RF_RF") (pintype "bidirectional"))
    )
    (net (code "98") (name "unconnected-(U1-PadUSBNA)") (class "Default")
      (node (ref "U1") (pin "USBNA") (pinfunction "USBNA_USBNA") (pintype "bidirectional"))
    )
    (net (code "99") (name "unconnected-(U1-PadUSBPA)") (class "Default")
      (node (ref "U1") (pin "USBPA") (pinfunction "USBPA_USBPA") (pintype "bidirectional"))
    )
    (net (code "100") (name "unconnected-(U1-PadVCC3IOA)") (class "Default")
      (node (ref "U1") (pin "VCC3IOA") (pinfunction "VCC3IOA_VCC3IOA") (pintype "bidirectional"))
    )
    (net (code "101") (name "unconnected-(U1-VCC3YS-PadVCCSYS)") (class "Default")
      (node (ref "U1") (pin "VCCSYS") (pinfunction "VCC3YS_VCCSYS") (pintype "bidirectional"))
    )
    (net (code "102") (name "unconnected-(U1-V_USB-PadVUSB)") (class "Default")
      (node (ref "U1") (pin "VUSB") (pinfunction "V_USB_VUSB") (pintype "bidirectional"))
    )
    (net (code "103") (name "unconnected-(U2-ADC6-Pad19)") (class "Default")
      (node (ref "U2") (pin "19") (pinfunction "ADC6_19") (pintype "bidirectional"))
    )
    (net (code "104") (name "unconnected-(U2-ADC7-Pad22)") (class "Default")
      (node (ref "U2") (pin "22") (pinfunction "ADC7_22") (pintype "bidirectional"))
    )
    (net (code "105") (name "unconnected-(U2-AREF-Pad20)") (class "Default")
      (node (ref "U2") (pin "20") (pinfunction "AREF_20") (pintype "passive"))
    )
    (net (code "106") (name "unconnected-(U2-PB2(SS{slash}OC1B)-Pad14)") (class "Default")
      (node (ref "U2") (pin "14") (pinfunction "PB2(SS/OC1B)_14") (pintype "bidirectional"))
    )
    (net (code "107") (name "unconnected-(U2-PC1(ADC1)-Pad24)") (class "Default")
      (node (ref "U2") (pin "24") (pinfunction "PC1(ADC1)_24") (pintype "bidirectional"))
    )
    (net (code "108") (name "unconnected-(U2-PC2(ADC2)-Pad25)") (class "Default")
      (node (ref "U2") (pin "25") (pinfunction "PC2(ADC2)_25") (pintype "bidirectional"))
    )
    (net (code "109") (name "unconnected-(U2-PC3(ADC3)-Pad26)") (class "Default")
      (node (ref "U2") (pin "26") (pinfunction "PC3(ADC3)_26") (pintype "bidirectional"))
    )
    (net (code "110") (name "unconnected-(U2-PC4(ADC4{slash}SDA)-Pad27)") (class "Default")
      (node (ref "U2") (pin "27") (pinfunction "PC4(ADC4/SDA)_27") (pintype "bidirectional"))
    )
    (net (code "111") (name "unconnected-(U2-PC5(ADC5{slash}SCL)-Pad28)") (class "Default")
      (node (ref "U2") (pin "28") (pinfunction "PC5(ADC5/SCL)_28") (pintype "bidirectional"))
    )
    (net (code "112") (name "unconnected-(U6-OUT1-PadTAB)") (class "Default")
      (node (ref "U6") (pin "TAB") (pinfunction "OUT1_TAB") (pintype "passive"))
    )
    (net (code "113") (name "unconnected-(X4-Pad3)") (class "Default")
      (node (ref "X4") (pin "3") (pinfunction "3_3") (pintype "passive"))
    )
    (net (code "114") (name "unconnected-(X4-Pad4)") (class "Default")
      (node (ref "X4") (pin "4") (pinfunction "4_4") (pintype "passive"))
    )
  )
)
